# espMDL_MCP3425_2C.net
KiCad netlist of a schematic drawn in EAGLE
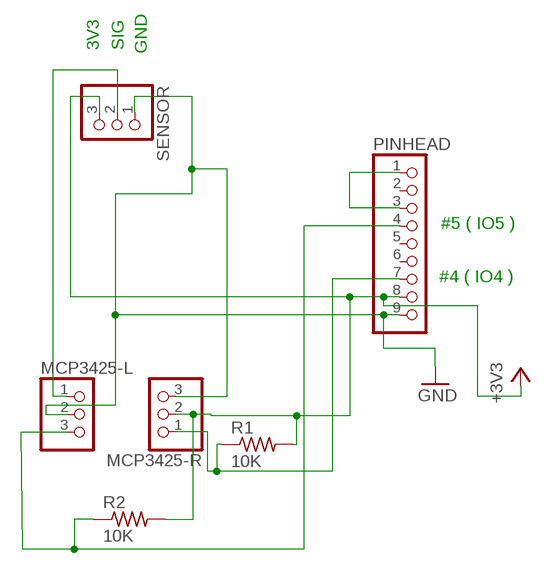
[diagram p0: schematic, sheet 1]

(export (version "E")
  (design (tool "Eeschema 10.0.6"))
  (components
    (comp (ref "MCP3425-L")
      (value "PINHD-1X3")
      (footprint "eagle-import:1X03")
      (libsource (lib "eagle-import") (part "PINHD-1X3"))
    )
    (comp (ref "MCP3425-R")
      (value "PINHD-1X3")
      (footprint "eagle-import:1X03")
      (libsource (lib "eagle-import") (part "PINHD-1X3"))
    )
    (comp (ref "PINHEAD")
      (value "PINHD-1X9")
      (footprint "eagle-import:1X09")
      (libsource (lib "eagle-import") (part "PINHD-1X9"))
    )
    (comp (ref "R1")
      (value "10K")
      (footprint "eagle-import:0204_7")
      (libsource (lib "eagle-import") (part "R-US_0204/7"))
    )
    (comp (ref "R2")
      (value "10K")
      (footprint "eagle-import:0204_7")
      (libsource (lib "eagle-import") (part "R-US_0204/7"))
    )
    (comp (ref "SENSOR")
      (value "PINHD-1X3")
      (footprint "eagle-import:1X03")
      (libsource (lib "eagle-import") (part "PINHD-1X3"))
    )
  )
  (nets
    (net (code "1") (name "+3V3") (class "Default")
      (node (ref "MCP3425-R") (pin "2") (pinfunction "2_2") (pintype "passive"))
      (node (ref "PINHEAD") (pin "8") (pinfunction "8_8") (pintype "passive"))
      (node (ref "R1") (pin "2") (pinfunction "2_2") (pintype "passive"))
      (node (ref "R2") (pin "2") (pinfunction "2_2") (pintype "passive"))
      (node (ref "SENSOR") (pin "3") (pinfunction "3_3") (pintype "passive"))
    )
    (net (code "2") (name "GND") (class "Default")
      (node (ref "MCP3425-L") (pin "2") (pinfunction "2_2") (pintype "passive"))
      (node (ref "MCP3425-R") (pin "3") (pinfunction "3_3") (pintype "passive"))
      (node (ref "PINHEAD") (pin "9") (pinfunction "9_9") (pintype "passive"))
      (node (ref "SENSOR") (pin "1") (pinfunction "1_1") (pintype "passive"))
    )
    (net (code "3") (name "Net-(MCP3425-L-Pad1)") (class "Default")
      (node (ref "MCP3425-L") (pin "1") (pinfunction "1_1") (pintype "passive"))
      (node (ref "SENSOR") (pin "2") (pinfunction "2_2") (pintype "passive"))
    )
    (net (code "4") (name "Net-(MCP3425-L-Pad3)") (class "Default")
      (node (ref "MCP3425-L") (pin "3") (pinfunction "3_3") (pintype "passive"))
      (node (ref "PINHEAD") (pin "4") (pinfunction "4_4") (pintype "passive"))
      (node (ref "R2") (pin "1") (pinfunction "1_1") (pintype "passive"))
    )
    (net (code "5") (name "Net-(MCP3425-R-Pad1)") (class "Default")
      (node (ref "MCP3425-R") (pin "1") (pinfunction "1_1") (pintype "passive"))
      (node (ref "PINHEAD") (pin "7") (pinfunction "7_7") (pintype "passive"))
      (node (ref "R1") (pin "1") (pinfunction "1_1") (pintype "passive"))
    )
    (net (code "6") (name "Net-(PINHEAD-Pad1)") (class "Default")
      (node (ref "PINHEAD") (pin "1") (pinfunction "1_1") (pintype "passive"))
      (node (ref "PINHEAD") (pin "3") (pinfunction "3_3") (pintype "passive"))
    )
    (net (code "7") (name "unconnected-(PINHEAD-Pad2)") (class "Default")
      (node (ref "PINHEAD") (pin "2") (pinfunction "2_2") (pintype "passive"))
    )
    (net (code "8") (name "unconnected-(PINHEAD-Pad5)") (class "Default")
      (node (ref "PINHEAD") (pin "5") (pinfunction "5_5") (pintype "passive"))
    )
    (net (code "9") (name "unconnected-(PINHEAD-Pad6)") (class "Default")
      (node (ref "PINHEAD") (pin "6") (pinfunction "6_6") (pintype "passive"))
    )
  )
)
